# DRV10987.net
KiCad netlist of a schematic drawn in EAGLE
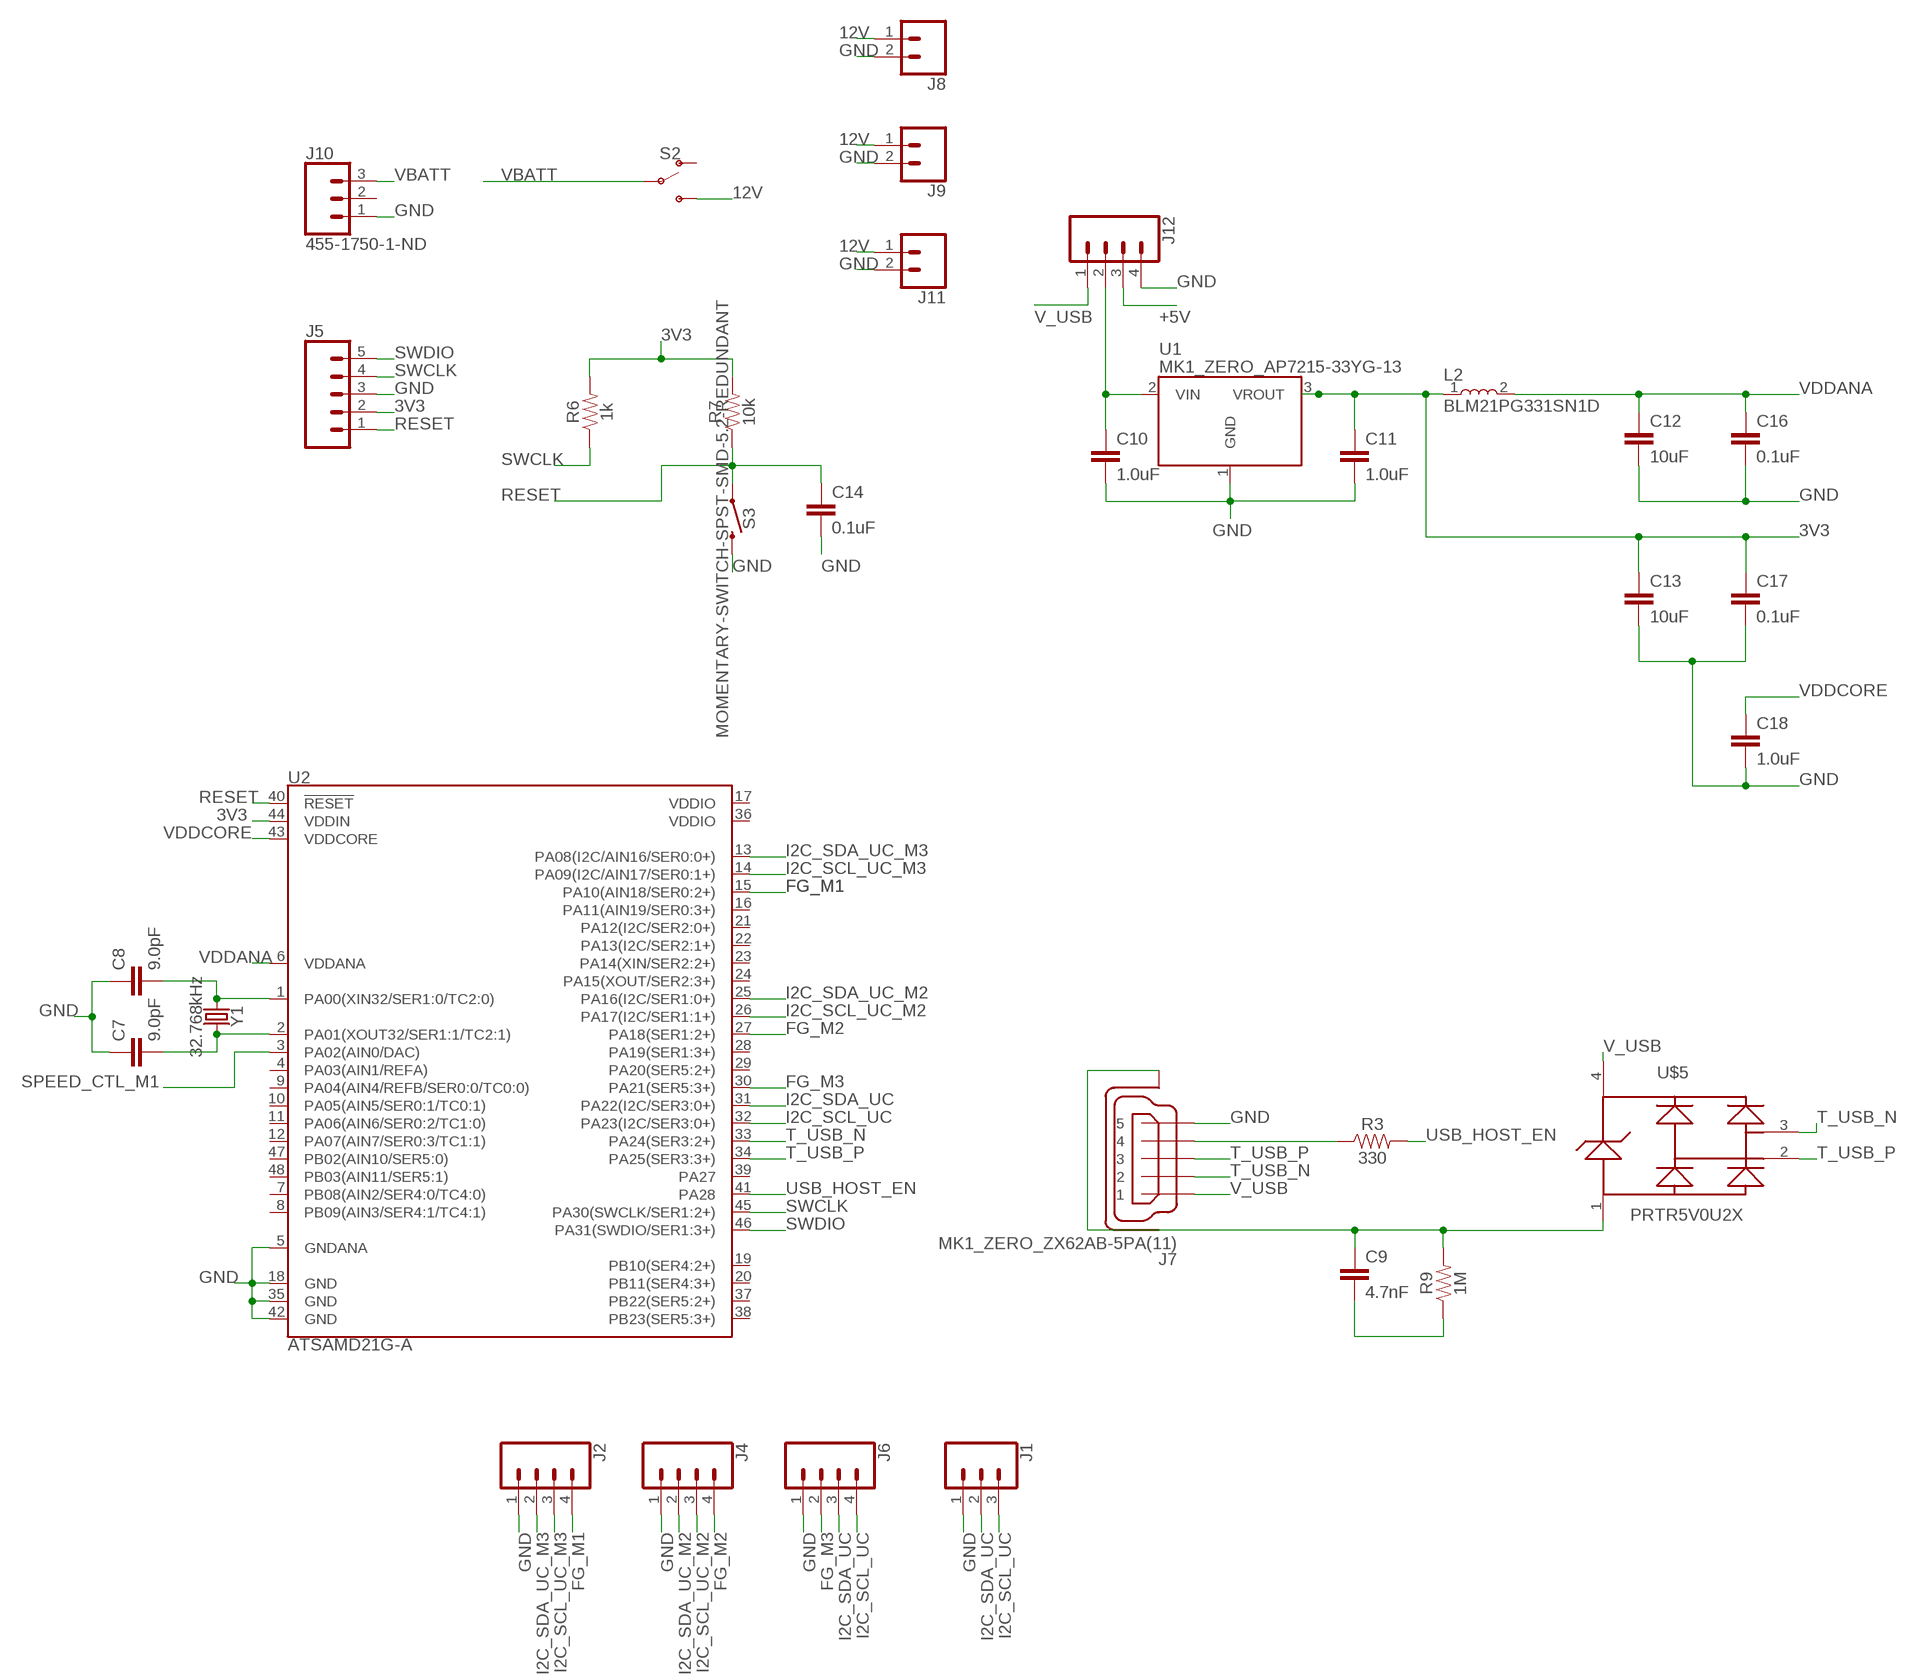
[diagram p0: schematic, sheet 1]

(export (version "E")
  (design (tool "Eeschema 10.0.6"))
  (components
    (comp (ref "C7")
      (value "9.0pF")
      (footprint "eagle-import:0603")
      (libsource (lib "eagle-import") (part "9.0PF-0603-50V-10%"))
    )
    (comp (ref "C8")
      (value "9.0pF")
      (footprint "eagle-import:0603")
      (libsource (lib "eagle-import") (part "9.0PF-0603-50V-10%"))
    )
    (comp (ref "C9")
      (value "4.7nF")
      (footprint "eagle-import:0603")
      (libsource (lib "eagle-import") (part "4.7PF-0603-50V-5%"))
    )
    (comp (ref "C10")
      (value "1.0uF")
      (footprint "eagle-import:0805")
      (libsource (lib "eagle-import") (part "1.0UF-0805-25V-(+80/-20%)"))
    )
    (comp (ref "C11")
      (value "1.0uF")
      (footprint "eagle-import:0805")
      (libsource (lib "eagle-import") (part "1.0UF-0805-25V-(+80/-20%)"))
    )
    (comp (ref "C12")
      (value "10uF")
      (footprint "eagle-import:0805")
      (libsource (lib "eagle-import") (part "10UF-0805-10V-10%"))
    )
    (comp (ref "C13")
      (value "10uF")
      (footprint "eagle-import:0805")
      (libsource (lib "eagle-import") (part "10UF-0805-10V-10%"))
    )
    (comp (ref "C14")
      (value "0.1uF")
      (footprint "eagle-import:0805")
      (libsource (lib "eagle-import") (part "1.0UF-0805-25V-(+80/-20%)"))
    )
    (comp (ref "C16")
      (value "0.1uF")
      (footprint "eagle-import:0805")
      (libsource (lib "eagle-import") (part "1.0UF-0805-25V-(+80/-20%)"))
    )
    (comp (ref "C17")
      (value "0.1uF")
      (footprint "eagle-import:0805")
      (libsource (lib "eagle-import") (part "1.0UF-0805-25V-(+80/-20%)"))
    )
    (comp (ref "C18")
      (value "1.0uF")
      (footprint "eagle-import:0805")
      (libsource (lib "eagle-import") (part "1.0UF-0805-25V-(+80/-20%)"))
    )
    (comp (ref "J1")
      (value "CONN_03LOCK")
      (footprint "eagle-import:1X03_LOCK")
      (libsource (lib "eagle-import") (part "CONN_03LOCK"))
    )
    (comp (ref "J2")
      (value "CONN_04LOCK")
      (footprint "eagle-import:1X04_LOCK")
      (libsource (lib "eagle-import") (part "CONN_04LOCK"))
    )
    (comp (ref "J4")
      (value "CONN_04LOCK")
      (footprint "eagle-import:1X04_LOCK")
      (libsource (lib "eagle-import") (part "CONN_04LOCK"))
    )
    (comp (ref "J5")
      (value "CONN_05LOCK_LONGPADS")
      (footprint "eagle-import:1X05_LOCK_LONGPADS")
      (libsource (lib "eagle-import") (part "CONN_05LOCK_LONGPADS"))
    )
    (comp (ref "J6")
      (value "CONN_04LOCK")
      (footprint "eagle-import:1X04_LOCK")
      (libsource (lib "eagle-import") (part "CONN_04LOCK"))
    )
    (comp (ref "J7")
      (value "MK1_ZERO_ZX62AB-5PA(11)")
      (footprint "eagle-import:MK1_ZERO_USBMICRO-ZX62-AB-5PA")
      (libsource (lib "eagle-import") (part "MK1_ZERO_ZX62AB-5PA(11)"))
    )
    (comp (ref "J8")
      (value "CONN_02LOCK")
      (footprint "eagle-import:1X02_LOCK")
      (libsource (lib "eagle-import") (part "CONN_02LOCK"))
    )
    (comp (ref "J9")
      (value "CONN_02LOCK")
      (footprint "eagle-import:1X02_LOCK")
      (libsource (lib "eagle-import") (part "CONN_02LOCK"))
    )
    (comp (ref "J10")
      (value "455-1750-1-ND")
      (footprint "eagle-import:1X03")
      (libsource (lib "eagle-import") (part "CONN_03"))
    )
    (comp (ref "J11")
      (value "CONN_02LOCK")
      (footprint "eagle-import:1X02_LOCK")
      (libsource (lib "eagle-import") (part "CONN_02LOCK"))
    )
    (comp (ref "J12")
      (value "CONN_04LOCK")
      (footprint "eagle-import:1X04_LOCK")
      (libsource (lib "eagle-import") (part "CONN_04LOCK"))
    )
    (comp (ref "L2")
      (value "BLM21PG331SN1D")
      (footprint "eagle-import:INDC2012X87")
      (fields (field (name "MANUFACTURER") "MURATA"))
      (libsource (lib "eagle-import") (part "BLM21PG331SN1D"))
    )
    (comp (ref "R3")
      (value "330")
      (footprint "eagle-import:0603")
      (libsource (lib "eagle-import") (part "330OHM-0603-1/10W-1%"))
    )
    (comp (ref "R6")
      (value "1k")
      (footprint "eagle-import:0603")
      (libsource (lib "eagle-import") (part "1KOHM-0603-1/10W-1%"))
    )
    (comp (ref "R7")
      (value "10k")
      (footprint "eagle-import:0603")
      (libsource (lib "eagle-import") (part "10KOHM-0603-1/10W-1%"))
    )
    (comp (ref "R9")
      (value "1M")
      (footprint "eagle-import:0603")
      (libsource (lib "eagle-import") (part "1MOHM-0603-1/4W-5%"))
    )
    (comp (ref "S2")
      (value "SWITCH-SPDT-PTH-11.6X4.0MM")
      (footprint "eagle-import:SWITCH_SPDT_PTH_11.6X4.0MM")
      (libsource (lib "eagle-import") (part "SWITCH-SPDT-PTH-11.6X4.0MM"))
    )
    (comp (ref "S3")
      (value "MOMENTARY-SWITCH-SPST-SMD-5.2-REDUNDANT")
      (footprint "eagle-import:TACTILE_SWITCH_SMD_5.2MM")
      (libsource (lib "eagle-import") (part "MOMENTARY-SWITCH-SPST-SMD-5.2-REDUNDANT"))
    )
    (comp (ref "U$5")
      (value "ARDUINO_PRTR5V0U2XB")
      (footprint "eagle-import:ARDUINO_SOT143B")
      (libsource (lib "eagle-import") (part "ARDUINO_PRTR5V0U2XB"))
    )
    (comp (ref "U1")
      (value "MK1_ZERO_AP7215-33YG-13")
      (footprint "eagle-import:MK1_ZERO_SOT150P400X160-3N")
      (fields (field (name "MF") "Diodes Inc ") (field (name "MPN") "AP7215-33YG-13 "))
      (libsource (lib "eagle-import") (part "MK1_ZERO_AP7215-33YG-13"))
    )
    (comp (ref "U2")
      (value "ATSAMD21G-A")
      (footprint "eagle-import:TQFP-48")
      (libsource (lib "eagle-import") (part "ATSAMD21G-A"))
    )
    (comp (ref "Y1")
      (value "32.768kHz")
      (footprint "eagle-import:CRYSTAL-SMD-3.2X1.5MM")
      (libsource (lib "eagle-import") (part "CRYSTAL-32.768KHZSMD-3.2X1.5"))
    )
  )
  (nets
    (net (code "1") (name "/+5V") (class "Default")
      (node (ref "J12") (pin "3") (pinfunction "3_3") (pintype "passive"))
    )
    (net (code "2") (name "/3V3") (class "Default")
      (node (ref "C11") (pin "1") (pinfunction "1_1") (pintype "passive"))
      (node (ref "C13") (pin "1") (pinfunction "1_1") (pintype "passive"))
      (node (ref "C17") (pin "1") (pinfunction "1_1") (pintype "passive"))
      (node (ref "J5") (pin "2") (pinfunction "2_2") (pintype "passive"))
      (node (ref "L2") (pin "1") (pinfunction "1_1") (pintype "passive"))
      (node (ref "R6") (pin "2") (pinfunction "2_2") (pintype "passive"))
      (node (ref "R7") (pin "2") (pinfunction "2_2") (pintype "passive"))
      (node (ref "U1") (pin "3") (pinfunction "VROUT_3") (pintype "power_in"))
      (node (ref "U2") (pin "44") (pinfunction "VDDIN_44") (pintype "bidirectional"))
    )
    (net (code "3") (name "/12V") (class "Default")
      (node (ref "J11") (pin "1") (pinfunction "1_1") (pintype "passive"))
      (node (ref "J8") (pin "1") (pinfunction "1_1") (pintype "passive"))
      (node (ref "J9") (pin "1") (pinfunction "1_1") (pintype "passive"))
      (node (ref "S2") (pin "3") (pinfunction "S_3") (pintype "passive"))
    )
    (net (code "4") (name "/FG_M1") (class "Default")
      (node (ref "J2") (pin "4") (pinfunction "4_4") (pintype "passive"))
      (node (ref "U2") (pin "15") (pinfunction "PA10(AIN18/SER0:2+)_15") (pintype "bidirectional"))
    )
    (net (code "5") (name "/FG_M2") (class "Default")
      (node (ref "J4") (pin "4") (pinfunction "4_4") (pintype "passive"))
      (node (ref "U2") (pin "27") (pinfunction "PA18(SER1:2+)_27") (pintype "bidirectional"))
    )
    (net (code "6") (name "/FG_M3") (class "Default")
      (node (ref "J6") (pin "2") (pinfunction "2_2") (pintype "passive"))
      (node (ref "U2") (pin "30") (pinfunction "PA21(SER5:3+)_30") (pintype "bidirectional"))
    )
    (net (code "7") (name "/GND") (class "Default")
      (node (ref "C10") (pin "2") (pinfunction "2_2") (pintype "passive"))
      (node (ref "C11") (pin "2") (pinfunction "2_2") (pintype "passive"))
      (node (ref "C12") (pin "2") (pinfunction "2_2") (pintype "passive"))
      (node (ref "C13") (pin "2") (pinfunction "2_2") (pintype "passive"))
      (node (ref "C14") (pin "2") (pinfunction "2_2") (pintype "passive"))
      (node (ref "C16") (pin "2") (pinfunction "2_2") (pintype "passive"))
      (node (ref "C17") (pin "2") (pinfunction "2_2") (pintype "passive"))
      (node (ref "C18") (pin "2") (pinfunction "2_2") (pintype "passive"))
      (node (ref "C7") (pin "1") (pinfunction "1_1") (pintype "passive"))
      (node (ref "C8") (pin "1") (pinfunction "1_1") (pintype "passive"))
      (node (ref "J1") (pin "1") (pinfunction "1_1") (pintype "passive"))
      (node (ref "J10") (pin "1") (pinfunction "1_1") (pintype "passive"))
      (node (ref "J11") (pin "2") (pinfunction "2_2") (pintype "passive"))
      (node (ref "J12") (pin "4") (pinfunction "4_4") (pintype "passive"))
      (node (ref "J2") (pin "1") (pinfunction "1_1") (pintype "passive"))
      (node (ref "J4") (pin "1") (pinfunction "1_1") (pintype "passive"))
      (node (ref "J5") (pin "3") (pinfunction "3_3") (pintype "passive"))
      (node (ref "J6") (pin "1") (pinfunction "1_1") (pintype "passive"))
      (node (ref "J7") (pin "5") (pinfunction "5_5") (pintype "passive"))
      (node (ref "J8") (pin "2") (pinfunction "2_2") (pintype "passive"))
      (node (ref "J9") (pin "2") (pinfunction "2_2") (pintype "passive"))
      (node (ref "S3") (pin "3") (pinfunction "2_3") (pintype "passive"))
      (node (ref "S3") (pin "4") (pinfunction "2_4") (pintype "passive"))
      (node (ref "U1") (pin "1") (pinfunction "GND_1") (pintype "power_in"))
      (node (ref "U2") (pin "18") (pinfunction "GND_18") (pintype "bidirectional"))
      (node (ref "U2") (pin "35") (pinfunction "GND_35") (pintype "bidirectional"))
      (node (ref "U2") (pin "42") (pinfunction "GND_42") (pintype "bidirectional"))
      (node (ref "U2") (pin "5") (pinfunction "GNDANA_5") (pintype "bidirectional"))
    )
    (net (code "8") (name "/I2C_SCL_UC") (class "Default")
      (node (ref "J1") (pin "3") (pinfunction "3_3") (pintype "passive"))
      (node (ref "J6") (pin "4") (pinfunction "4_4") (pintype "passive"))
      (node (ref "U2") (pin "32") (pinfunction "PA23(I2C/SER3:0+)_32") (pintype "bidirectional"))
    )
    (net (code "9") (name "/I2C_SCL_UC_M2") (class "Default")
      (node (ref "J4") (pin "3") (pinfunction "3_3") (pintype "passive"))
      (node (ref "U2") (pin "26") (pinfunction "PA17(I2C/SER1:1+)_26") (pintype "bidirectional"))
    )
    (net (code "10") (name "/I2C_SCL_UC_M3") (class "Default")
      (node (ref "J2") (pin "3") (pinfunction "3_3") (pintype "passive"))
      (node (ref "U2") (pin "14") (pinfunction "PA09(I2C/AIN17/SER0:1+)_14") (pintype "bidirectional"))
    )
    (net (code "11") (name "/I2C_SDA_UC") (class "Default")
      (node (ref "J1") (pin "2") (pinfunction "2_2") (pintype "passive"))
      (node (ref "J6") (pin "3") (pinfunction "3_3") (pintype "passive"))
      (node (ref "U2") (pin "31") (pinfunction "PA22(I2C/SER3:0+)_31") (pintype "bidirectional"))
    )
    (net (code "12") (name "/I2C_SDA_UC_M2") (class "Default")
      (node (ref "J4") (pin "2") (pinfunction "2_2") (pintype "passive"))
      (node (ref "U2") (pin "25") (pinfunction "PA16(I2C/SER1:0+)_25") (pintype "bidirectional"))
    )
    (net (code "13") (name "/I2C_SDA_UC_M3") (class "Default")
      (node (ref "J2") (pin "2") (pinfunction "2_2") (pintype "passive"))
      (node (ref "U2") (pin "13") (pinfunction "PA08(I2C/AIN16/SER0:0+)_13") (pintype "bidirectional"))
    )
    (net (code "14") (name "/RESET") (class "Default")
      (node (ref "C14") (pin "1") (pinfunction "1_1") (pintype "passive"))
      (node (ref "J5") (pin "1") (pinfunction "1_1") (pintype "passive"))
      (node (ref "R7") (pin "1") (pinfunction "1_1") (pintype "passive"))
      (node (ref "S3") (pin "1") (pinfunction "1_1") (pintype "passive"))
      (node (ref "S3") (pin "2") (pinfunction "1_2") (pintype "passive"))
      (node (ref "U2") (pin "40") (pinfunction "~{RESET}_40") (pintype "bidirectional"))
    )
    (net (code "15") (name "/SPEED_CTL_M1") (class "Default")
      (node (ref "U2") (pin "3") (pinfunction "PA02(AIN0/DAC)_3") (pintype "bidirectional"))
    )
    (net (code "16") (name "/SWCLK") (class "Default")
      (node (ref "J5") (pin "4") (pinfunction "4_4") (pintype "passive"))
      (node (ref "R6") (pin "1") (pinfunction "1_1") (pintype "passive"))
      (node (ref "U2") (pin "45") (pinfunction "PA30(SWCLK/SER1:2+)_45") (pintype "bidirectional"))
    )
    (net (code "17") (name "/SWDIO") (class "Default")
      (node (ref "J5") (pin "5") (pinfunction "5_5") (pintype "passive"))
      (node (ref "U2") (pin "46") (pinfunction "PA31(SWDIO/SER1:3+)_46") (pintype "bidirectional"))
    )
    (net (code "18") (name "/T_USB_N") (class "Default")
      (node (ref "J7") (pin "2") (pinfunction "2_2") (pintype "passive"))
      (node (ref "U$5") (pin "3") (pinfunction "3_3") (pintype "bidirectional"))
      (node (ref "U2") (pin "33") (pinfunction "PA24(SER3:2+)_33") (pintype "bidirectional"))
    )
    (net (code "19") (name "/T_USB_P") (class "Default")
      (node (ref "J7") (pin "3") (pinfunction "3_3") (pintype "passive"))
      (node (ref "U$5") (pin "2") (pinfunction "2_2") (pintype "bidirectional"))
      (node (ref "U2") (pin "34") (pinfunction "PA25(SER3:3+)_34") (pintype "bidirectional"))
    )
    (net (code "20") (name "/USB_HOST_EN") (class "Default")
      (node (ref "R3") (pin "2") (pinfunction "2_2") (pintype "passive"))
      (node (ref "U2") (pin "41") (pinfunction "PA28_41") (pintype "bidirectional"))
    )
    (net (code "21") (name "/VBATT") (class "Default")
      (node (ref "J10") (pin "3") (pinfunction "3_3") (pintype "passive"))
      (node (ref "S2") (pin "2") (pinfunction "P_2") (pintype "passive"))
    )
    (net (code "22") (name "/VDDANA") (class "Default")
      (node (ref "C12") (pin "1") (pinfunction "1_1") (pintype "passive"))
      (node (ref "C16") (pin "1") (pinfunction "1_1") (pintype "passive"))
      (node (ref "L2") (pin "2") (pinfunction "2_2") (pintype "passive"))
      (node (ref "U2") (pin "6") (pinfunction "VDDANA_6") (pintype "bidirectional"))
    )
    (net (code "23") (name "/VDDCORE") (class "Default")
      (node (ref "C18") (pin "1") (pinfunction "1_1") (pintype "passive"))
      (node (ref "U2") (pin "43") (pinfunction "VDDCORE_43") (pintype "bidirectional"))
    )
    (net (code "24") (name "/V_USB") (class "Default")
      (node (ref "J12") (pin "1") (pinfunction "1_1") (pintype "passive"))
      (node (ref "J7") (pin "1") (pinfunction "1_1") (pintype "passive"))
      (node (ref "U$5") (pin "4") (pinfunction "4_4") (pintype "bidirectional"))
    )
    (net (code "25") (name "Net-(C9-Pad1)") (class "Default")
      (node (ref "C9") (pin "1") (pinfunction "1_1") (pintype "passive"))
      (node (ref "J7") (pin "10") (pinfunction "SH_10") (pintype "passive"))
      (node (ref "J7") (pin "11") (pinfunction "SH_11") (pintype "passive"))
      (node (ref "J7") (pin "6") (pinfunction "SH_6") (pintype "passive"))
      (node (ref "J7") (pin "7") (pinfunction "SH_7") (pintype "passive"))
      (node (ref "J7") (pin "8") (pinfunction "SH_8") (pintype "passive"))
      (node (ref "J7") (pin "9") (pinfunction "SH_9") (pintype "passive"))
      (node (ref "R9") (pin "2") (pinfunction "2_2") (pintype "passive"))
      (node (ref "U$5") (pin "1") (pinfunction "1_1") (pintype "bidirectional"))
    )
    (net (code "26") (name "Net-(C9-Pad2)") (class "Default")
      (node (ref "C9") (pin "2") (pinfunction "2_2") (pintype "passive"))
      (node (ref "R9") (pin "1") (pinfunction "1_1") (pintype "passive"))
    )
    (net (code "27") (name "Net-(J7-Pad4)") (class "Default")
      (node (ref "J7") (pin "4") (pinfunction "4_4") (pintype "passive"))
      (node (ref "R3") (pin "1") (pinfunction "1_1") (pintype "passive"))
    )
    (net (code "28") (name "Net-(U1-VIN)") (class "Default")
      (node (ref "C10") (pin "1") (pinfunction "1_1") (pintype "passive"))
      (node (ref "J12") (pin "2") (pinfunction "2_2") (pintype "passive"))
      (node (ref "U1") (pin "2") (pinfunction "VIN_2") (pintype "power_in"))
    )
    (net (code "29") (name "Net-(U2-PA00(XIN32{slash}SER1:0{slash}TC2:0))") (class "Default")
      (node (ref "C8") (pin "2") (pinfunction "2_2") (pintype "passive"))
      (node (ref "U2") (pin "1") (pinfunction "PA00(XIN32/SER1:0/TC2:0)_1") (pintype "bidirectional"))
      (node (ref "Y1") (pin "P$1") (pinfunction "1_P$1") (pintype "passive"))
    )
    (net (code "30") (name "Net-(U2-PA01(XOUT32{slash}SER1:1{slash}TC2:1))") (class "Default")
      (node (ref "C7") (pin "2") (pinfunction "2_2") (pintype "passive"))
      (node (ref "U2") (pin "2") (pinfunction "PA01(XOUT32/SER1:1/TC2:1)_2") (pintype "bidirectional"))
      (node (ref "Y1") (pin "P$2") (pinfunction "2_P$2") (pintype "passive"))
    )
    (net (code "31") (name "unconnected-(J10-Pad2)") (class "Default")
      (node (ref "J10") (pin "2") (pinfunction "2_2") (pintype "passive"))
    )
    (net (code "32") (name "unconnected-(S2-O-Pad1)") (class "Default")
      (node (ref "S2") (pin "1") (pinfunction "O_1") (pintype "passive"))
    )
    (net (code "33") (name "unconnected-(U2-PA03(AIN1{slash}REFA)-Pad4)") (class "Default")
      (node (ref "U2") (pin "4") (pinfunction "PA03(AIN1/REFA)_4") (pintype "bidirectional"))
    )
    (net (code "34") (name "unconnected-(U2-PA04(AIN4{slash}REFB{slash}SER0:0{slash}TC0:0)-Pad9)") (class "Default")
      (node (ref "U2") (pin "9") (pinfunction "PA04(AIN4/REFB/SER0:0/TC0:0)_9") (pintype "bidirectional"))
    )
    (net (code "35") (name "unconnected-(U2-PA05(AIN5{slash}SER0:1{slash}TC0:1)-Pad10)") (class "Default")
      (node (ref "U2") (pin "10") (pinfunction "PA05(AIN5/SER0:1/TC0:1)_10") (pintype "bidirectional"))
    )
    (net (code "36") (name "unconnected-(U2-PA06(AIN6{slash}SER0:2{slash}TC1:0)-Pad11)") (class "Default")
      (node (ref "U2") (pin "11") (pinfunction "PA06(AIN6/SER0:2/TC1:0)_11") (pintype "bidirectional"))
    )
    (net (code "37") (name "unconnected-(U2-PA07(AIN7{slash}SER0:3{slash}TC1:1)-Pad12)") (class "Default")
      (node (ref "U2") (pin "12") (pinfunction "PA07(AIN7/SER0:3/TC1:1)_12") (pintype "bidirectional"))
    )
    (net (code "38") (name "unconnected-(U2-PA11(AIN19{slash}SER0:3+)-Pad16)") (class "Default")
      (node (ref "U2") (pin "16") (pinfunction "PA11(AIN19/SER0:3+)_16") (pintype "bidirectional"))
    )
    (net (code "39") (name "unconnected-(U2-PA12(I2C{slash}SER2:0+)-Pad21)") (class "Default")
      (node (ref "U2") (pin "21") (pinfunction "PA12(I2C/SER2:0+)_21") (pintype "bidirectional"))
    )
    (net (code "40") (name "unconnected-(U2-PA13(I2C{slash}SER2:1+)-Pad22)") (class "Default")
      (node (ref "U2") (pin "22") (pinfunction "PA13(I2C/SER2:1+)_22") (pintype "bidirectional"))
    )
    (net (code "41") (name "unconnected-(U2-PA14(XIN{slash}SER2:2+)-Pad23)") (class "Default")
      (node (ref "U2") (pin "23") (pinfunction "PA14(XIN/SER2:2+)_23") (pintype "bidirectional"))
    )
    (net (code "42") (name "unconnected-(U2-PA15(XOUT{slash}SER2:3+)-Pad24)") (class "Default")
      (node (ref "U2") (pin "24") (pinfunction "PA15(XOUT/SER2:3+)_24") (pintype "bidirectional"))
    )
    (net (code "43") (name "unconnected-(U2-PA19(SER1:3+)-Pad28)") (class "Default")
      (node (ref "U2") (pin "28") (pinfunction "PA19(SER1:3+)_28") (pintype "bidirectional"))
    )
    (net (code "44") (name "unconnected-(U2-PA20(SER5:2+)-Pad29)") (class "Default")
      (node (ref "U2") (pin "29") (pinfunction "PA20(SER5:2+)_29") (pintype "bidirectional"))
    )
    (net (code "45") (name "unconnected-(U2-PA27-Pad39)") (class "Default")
      (node (ref "U2") (pin "39") (pinfunction "PA27_39") (pintype "bidirectional"))
    )
    (net (code "46") (name "unconnected-(U2-PB02(AIN10{slash}SER5:0)-Pad47)") (class "Default")
      (node (ref "U2") (pin "47") (pinfunction "PB02(AIN10/SER5:0)_47") (pintype "bidirectional"))
    )
    (net (code "47") (name "unconnected-(U2-PB03(AIN11{slash}SER5:1)-Pad48)") (class "Default")
      (node (ref "U2") (pin "48") (pinfunction "PB03(AIN11/SER5:1)_48") (pintype "bidirectional"))
    )
    (net (code "48") (name "unconnected-(U2-PB08(AIN2{slash}SER4:0{slash}TC4:0)-Pad7)") (class "Default")
      (node (ref "U2") (pin "7") (pinfunction "PB08(AIN2/SER4:0/TC4:0)_7") (pintype "bidirectional"))
    )
    (net (code "49") (name "unconnected-(U2-PB09(AIN3{slash}SER4:1{slash}TC4:1)-Pad8)") (class "Default")
      (node (ref "U2") (pin "8") (pinfunction "PB09(AIN3/SER4:1/TC4:1)_8") (pintype "bidirectional"))
    )
    (net (code "50") (name "unconnected-(U2-PB10(SER4:2+)-Pad19)") (class "Default")
      (node (ref "U2") (pin "19") (pinfunction "PB10(SER4:2+)_19") (pintype "bidirectional"))
    )
    (net (code "51") (name "unconnected-(U2-PB11(SER4:3+)-Pad20)") (class "Default")
      (node (ref "U2") (pin "20") (pinfunction "PB11(SER4:3+)_20") (pintype "bidirectional"))
    )
    (net (code "52") (name "unconnected-(U2-PB22(SER5:2+)-Pad37)") (class "Default")
      (node (ref "U2") (pin "37") (pinfunction "PB22(SER5:2+)_37") (pintype "bidirectional"))
    )
    (net (code "53") (name "unconnected-(U2-PB23(SER5:3+)-Pad38)") (class "Default")
      (node (ref "U2") (pin "38") (pinfunction "PB23(SER5:3+)_38") (pintype "bidirectional"))
    )
    (net (code "54") (name "unconnected-(U2-VDDIO-Pad17)") (class "Default")
      (node (ref "U2") (pin "17") (pinfunction "VDDIO_17") (pintype "bidirectional"))
    )
    (net (code "55") (name "unconnected-(U2-VDDIO-Pad36)") (class "Default")
      (node (ref "U2") (pin "36") (pinfunction "VDDIO_36") (pintype "bidirectional"))
    )
  )
)
